# Enclosure_85x58_WS.net
KiCad netlist of a schematic drawn in EAGLE
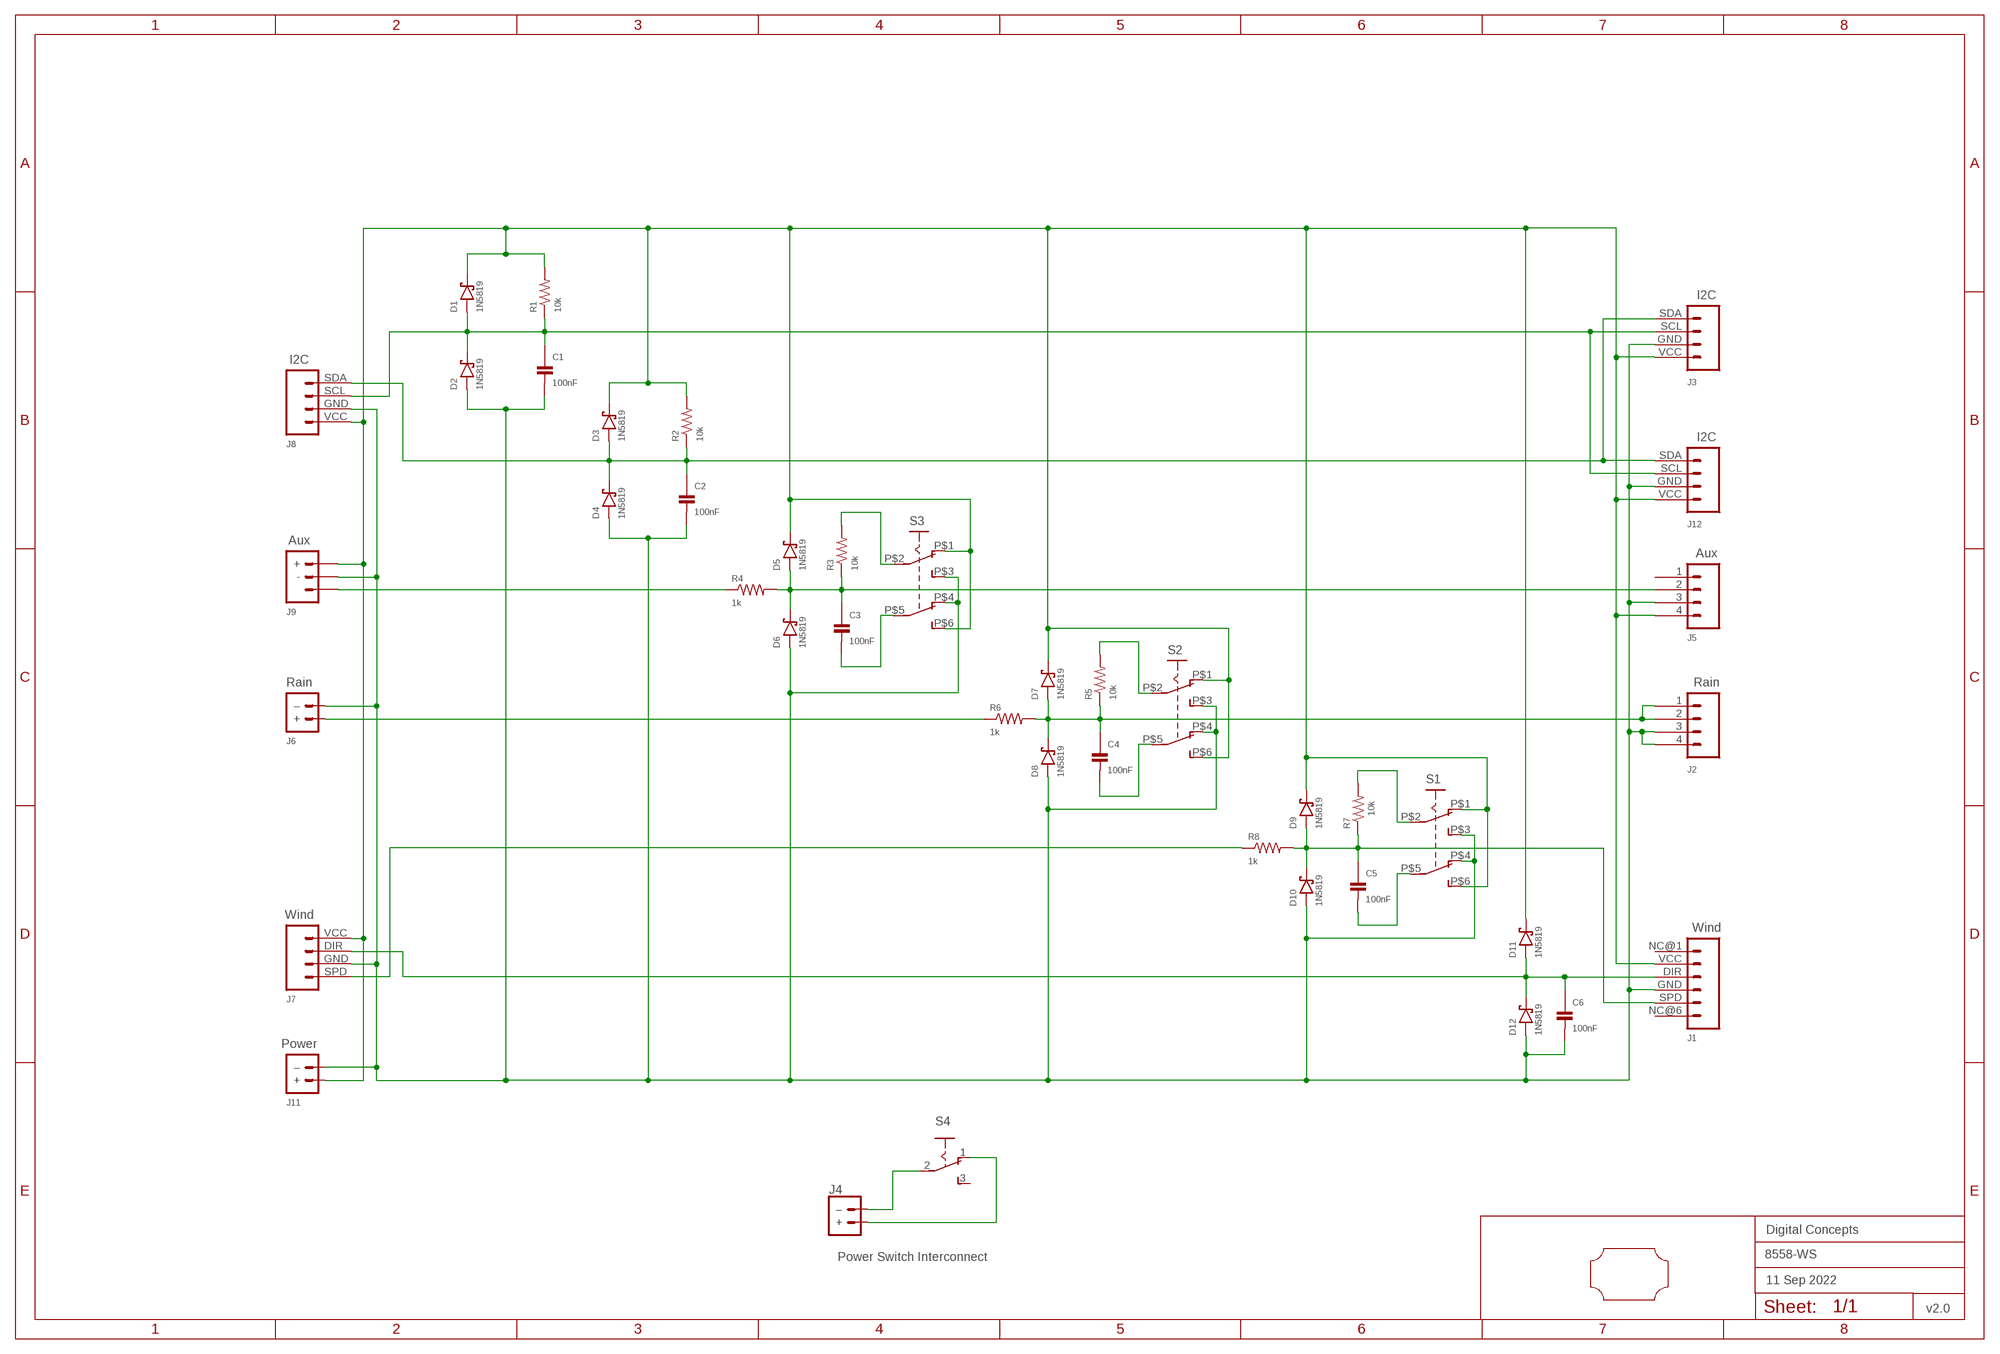
[diagram p0: schematic, sheet 1]

(export (version "E")
  (design (tool "Eeschema 10.0.6"))
  (components
    (comp (ref "C1")
      (value "100nF")
      (footprint "eagle-import:C0805-VIA-2")
      (libsource (lib "eagle-import") (part "CAPACITOR-0805-VIA-2"))
    )
    (comp (ref "C2")
      (value "100nF")
      (footprint "eagle-import:C0805-VIA-2")
      (libsource (lib "eagle-import") (part "CAPACITOR-0805-VIA-2"))
    )
    (comp (ref "C3")
      (value "100nF")
      (footprint "eagle-import:C0805")
      (libsource (lib "eagle-import") (part "CAPACITOR-0805"))
    )
    (comp (ref "C4")
      (value "100nF")
      (footprint "eagle-import:C0805")
      (libsource (lib "eagle-import") (part "CAPACITOR-0805"))
    )
    (comp (ref "C5")
      (value "100nF")
      (footprint "eagle-import:C0805")
      (libsource (lib "eagle-import") (part "CAPACITOR-0805"))
    )
    (comp (ref "C6")
      (value "100nF")
      (footprint "eagle-import:C0805-VIA-2")
      (libsource (lib "eagle-import") (part "CAPACITOR-0805-VIA-2"))
    )
    (comp (ref "D1")
      (value "1N5819")
      (footprint "eagle-import:SOD-123")
      (libsource (lib "eagle-import") (part "DIODE-SCHOTTKY-1N5819"))
    )
    (comp (ref "D2")
      (value "1N5819")
      (footprint "eagle-import:SOD-123-VIA-A")
      (libsource (lib "eagle-import") (part "DIODE-SCHOTTKY-1N5819-VIA-A"))
    )
    (comp (ref "D3")
      (value "1N5819")
      (footprint "eagle-import:SOD-123")
      (libsource (lib "eagle-import") (part "DIODE-SCHOTTKY-1N5819"))
    )
    (comp (ref "D4")
      (value "1N5819")
      (footprint "eagle-import:SOD-123-VIA-A")
      (libsource (lib "eagle-import") (part "DIODE-SCHOTTKY-1N5819-VIA-A"))
    )
    (comp (ref "D5")
      (value "1N5819")
      (footprint "eagle-import:SOD-123")
      (libsource (lib "eagle-import") (part "DIODE-SCHOTTKY-1N5819"))
    )
    (comp (ref "D6")
      (value "1N5819")
      (footprint "eagle-import:SOD-123-VIA-A")
      (libsource (lib "eagle-import") (part "DIODE-SCHOTTKY-1N5819-VIA-A"))
    )
    (comp (ref "D7")
      (value "1N5819")
      (footprint "eagle-import:SOD-123")
      (libsource (lib "eagle-import") (part "DIODE-SCHOTTKY-1N5819"))
    )
    (comp (ref "D8")
      (value "1N5819")
      (footprint "eagle-import:SOD-123-VIA-A")
      (libsource (lib "eagle-import") (part "DIODE-SCHOTTKY-1N5819-VIA-A"))
    )
    (comp (ref "D9")
      (value "1N5819")
      (footprint "eagle-import:SOD-123")
      (libsource (lib "eagle-import") (part "DIODE-SCHOTTKY-1N5819"))
    )
    (comp (ref "D10")
      (value "1N5819")
      (footprint "eagle-import:SOD-123-VIA-A")
      (libsource (lib "eagle-import") (part "DIODE-SCHOTTKY-1N5819-VIA-A"))
    )
    (comp (ref "D11")
      (value "1N5819")
      (footprint "eagle-import:SOD-123")
      (libsource (lib "eagle-import") (part "DIODE-SCHOTTKY-1N5819"))
    )
    (comp (ref "D12")
      (value "1N5819")
      (footprint "eagle-import:SOD-123-VIA-A")
      (libsource (lib "eagle-import") (part "DIODE-SCHOTTKY-1N5819-VIA-A"))
    )
    (comp (ref "J1")
      (value "Wind")
      (footprint "eagle-import:RJ11-6-VERTICAL-WIND")
      (libsource (lib "eagle-import") (part "RJ11-6P6C-VERTICAL-WIND"))
    )
    (comp (ref "J2")
      (value "Rain")
      (footprint "eagle-import:RJ11-4-VERTICAL")
      (libsource (lib "eagle-import") (part "RJ11-6P4C-VERTICAL"))
    )
    (comp (ref "J3")
      (value "I2C")
      (footprint "eagle-import:RJ11-4-VERTICAL-I2C")
      (libsource (lib "eagle-import") (part "RJ11-6P4C-VERTICAL-I2C"))
    )
    (comp (ref "J4")
      (value "JST-PH2.0-2-HORIZONTALJST-PTH-2")
      (footprint "eagle-import:JST-PH2.0-2-HORIZONTAL")
      (libsource (lib "eagle-import") (part "JST-PH2.0-2-HORIZONTALJST-PTH-2"))
    )
    (comp (ref "J5")
      (value "Aux")
      (footprint "eagle-import:RJ11-4-VERTICAL")
      (libsource (lib "eagle-import") (part "RJ11-6P4C-VERTICAL"))
    )
    (comp (ref "J6")
      (value "Rain")
      (footprint "eagle-import:JST-PH2.0-2-DUAL-POWER")
      (libsource (lib "eagle-import") (part "JST-PH2.0-2-DUALJST-PTH-2"))
    )
    (comp (ref "J7")
      (value "Wind")
      (footprint "eagle-import:JST-PH2.0-4-DUAL-WIND")
      (libsource (lib "eagle-import") (part "JST-PH2.0-4-DUAL-WIND"))
    )
    (comp (ref "J8")
      (value "I2C")
      (footprint "eagle-import:JST-PH2.0-4-DUAL-I2C")
      (libsource (lib "eagle-import") (part "JST-PH2.0-4-DUAL-I2C"))
    )
    (comp (ref "J9")
      (value "Aux")
      (footprint "eagle-import:JST-PH2.0-3-DUAL")
      (libsource (lib "eagle-import") (part "JST-PH2.0-3-DUAL"))
    )
    (comp (ref "J11")
      (value "Power")
      (footprint "eagle-import:JST-PH2.0-2-DUAL-POWER")
      (libsource (lib "eagle-import") (part "JST-PH2.0-2-DUALJST-PTH-2"))
    )
    (comp (ref "J12")
      (value "I2C")
      (footprint "eagle-import:CONN_04-I2C")
      (libsource (lib "eagle-import") (part "HEADER-1X4-I2C"))
    )
    (comp (ref "R1")
      (value "10k")
      (footprint "eagle-import:R0805-VIA-1")
      (libsource (lib "eagle-import") (part "RESISTOR-VIA-1"))
    )
    (comp (ref "R2")
      (value "10k")
      (footprint "eagle-import:R0805-VIA-1")
      (libsource (lib "eagle-import") (part "RESISTOR-VIA-1"))
    )
    (comp (ref "R3")
      (value "10k")
      (footprint "eagle-import:R0805")
      (libsource (lib "eagle-import") (part "RESISTORR0805"))
    )
    (comp (ref "R4")
      (value "1k")
      (footprint "eagle-import:R0805-VIA-1")
      (libsource (lib "eagle-import") (part "RESISTOR-VIA-1"))
    )
    (comp (ref "R5")
      (value "10k")
      (footprint "eagle-import:R0805")
      (libsource (lib "eagle-import") (part "RESISTORR0805"))
    )
    (comp (ref "R6")
      (value "1k")
      (footprint "eagle-import:R0805-VIA-1")
      (libsource (lib "eagle-import") (part "RESISTOR-VIA-1"))
    )
    (comp (ref "R7")
      (value "10k")
      (footprint "eagle-import:R0805")
      (libsource (lib "eagle-import") (part "RESISTORR0805"))
    )
    (comp (ref "R8")
      (value "1k")
      (footprint "eagle-import:R0805-VIA-1")
      (libsource (lib "eagle-import") (part "RESISTOR-VIA-1"))
    )
    (comp (ref "S1")
      (value "SWITCH-SLIDE-DPDT")
      (footprint "eagle-import:SWITCH-DPDT-SMD")
      (libsource (lib "eagle-import") (part "SWITCH-SLIDE-DPDT"))
    )
    (comp (ref "S2")
      (value "SWITCH-SLIDE-DPDT")
      (footprint "eagle-import:SWITCH-DPDT-SMD")
      (libsource (lib "eagle-import") (part "SWITCH-SLIDE-DPDT"))
    )
    (comp (ref "S3")
      (value "SWITCH-SLIDE-DPDT")
      (footprint "eagle-import:SWITCH-DPDT-SMD")
      (libsource (lib "eagle-import") (part "SWITCH-SLIDE-DPDT"))
    )
    (comp (ref "S4")
      (value "SWITCH-SLIDE-SPDT")
      (footprint "eagle-import:SWITCH-SPDT-PTH")
      (libsource (lib "eagle-import") (part "SWITCH-SLIDE-SPDT"))
    )
    (comp (ref "U$1")
      (value "PCB-OUTLINE-85X58")
      (footprint "eagle-import:PROTO-28X18-OUTLINE")
      (libsource (lib "eagle-import") (part "PCB-OUTLINE-85X58"))
    )
  )
  (nets
    (net (code "1") (name "Net-(J1-2)") (class "Default")
      (node (ref "D1") (pin "C") (pinfunction "C_C") (pintype "passive"))
      (node (ref "D11") (pin "C") (pinfunction "C_C") (pintype "passive"))
      (node (ref "D3") (pin "C") (pinfunction "C_C") (pintype "passive"))
      (node (ref "D5") (pin "C") (pinfunction "C_C") (pintype "passive"))
      (node (ref "D7") (pin "C") (pinfunction "C_C") (pintype "passive"))
      (node (ref "D9") (pin "C") (pinfunction "C_C") (pintype "passive"))
      (node (ref "J1") (pin "VCC") (pinfunction "2_VCC") (pintype "passive"))
      (node (ref "J11") (pin "+") (pinfunction "+_+") (pintype "power_in"))
      (node (ref "J12") (pin "VCC") (pinfunction "1_VCC") (pintype "passive"))
      (node (ref "J3") (pin "VCC") (pinfunction "1_VCC") (pintype "passive"))
      (node (ref "J5") (pin "4") (pinfunction "1_4") (pintype "passive"))
      (node (ref "J7") (pin "VCC") (pinfunction "1_VCC") (pintype "passive"))
      (node (ref "J8") (pin "VCC") (pinfunction "4_VCC") (pintype "passive"))
      (node (ref "J9") (pin "+") (pinfunction "+_+") (pintype "power_in"))
      (node (ref "R1") (pin "2") (pinfunction "2_2") (pintype "passive"))
      (node (ref "R2") (pin "2") (pinfunction "2_2") (pintype "passive"))
      (node (ref "S1") (pin "P$1") (pinfunction "O1_P$1") (pintype "passive"))
      (node (ref "S1") (pin "P$6") (pinfunction "S2_P$6") (pintype "passive"))
      (node (ref "S2") (pin "P$1") (pinfunction "O1_P$1") (pintype "passive"))
      (node (ref "S2") (pin "P$6") (pinfunction "S2_P$6") (pintype "passive"))
      (node (ref "S3") (pin "P$1") (pinfunction "O1_P$1") (pintype "passive"))
      (node (ref "S3") (pin "P$6") (pinfunction "S2_P$6") (pintype "passive"))
    )
    (net (code "2") (name "Net-(J1-3)") (class "Default")
      (node (ref "C6") (pin "1") (pinfunction "1_1") (pintype "passive"))
      (node (ref "D11") (pin "A") (pinfunction "A_A") (pintype "passive"))
      (node (ref "D12") (pin "C") (pinfunction "C_C") (pintype "passive"))
      (node (ref "J1") (pin "DIR") (pinfunction "3_DIR") (pintype "passive"))
      (node (ref "J7") (pin "DIR") (pinfunction "2_DIR") (pintype "passive"))
    )
    (net (code "3") (name "Net-(J1-4)") (class "Default")
      (node (ref "C1") (pin "2") (pinfunction "2_2") (pintype "passive"))
      (node (ref "C1") (pin "2@VIA") (pinfunction "2_2@VIA") (pintype "passive"))
      (node (ref "C2") (pin "2") (pinfunction "2_2") (pintype "passive"))
      (node (ref "C2") (pin "2@VIA") (pinfunction "2_2@VIA") (pintype "passive"))
      (node (ref "C6") (pin "2") (pinfunction "2_2") (pintype "passive"))
      (node (ref "C6") (pin "2@VIA") (pinfunction "2_2@VIA") (pintype "passive"))
      (node (ref "D10") (pin "A") (pinfunction "A_A") (pintype "passive"))
      (node (ref "D10") (pin "P$A") (pinfunction "A_P$A") (pintype "passive"))
      (node (ref "D12") (pin "A") (pinfunction "A_A") (pintype "passive"))
      (node (ref "D12") (pin "P$A") (pinfunction "A_P$A") (pintype "passive"))
      (node (ref "D2") (pin "A") (pinfunction "A_A") (pintype "passive"))
      (node (ref "D2") (pin "P$A") (pinfunction "A_P$A") (pintype "passive"))
      (node (ref "D4") (pin "A") (pinfunction "A_A") (pintype "passive"))
      (node (ref "D4") (pin "P$A") (pinfunction "A_P$A") (pintype "passive"))
      (node (ref "D6") (pin "A") (pinfunction "A_A") (pintype "passive"))
      (node (ref "D6") (pin "P$A") (pinfunction "A_P$A") (pintype "passive"))
      (node (ref "D8") (pin "A") (pinfunction "A_A") (pintype "passive"))
      (node (ref "D8") (pin "P$A") (pinfunction "A_P$A") (pintype "passive"))
      (node (ref "J1") (pin "GND") (pinfunction "4_GND") (pintype "passive"))
      (node (ref "J11") (pin "-") (pinfunction "–_-") (pintype "power_in"))
      (node (ref "J12") (pin "GND") (pinfunction "2_GND") (pintype "passive"))
      (node (ref "J2") (pin "3") (pinfunction "2_3") (pintype "passive"))
      (node (ref "J2") (pin "4") (pinfunction "1_4") (pintype "passive"))
      (node (ref "J3") (pin "GND") (pinfunction "2_GND") (pintype "passive"))
      (node (ref "J5") (pin "3") (pinfunction "2_3") (pintype "passive"))
      (node (ref "J6") (pin "-") (pinfunction "–_-") (pintype "power_in"))
      (node (ref "J7") (pin "GND") (pinfunction "3_GND") (pintype "passive"))
      (node (ref "J8") (pin "GND") (pinfunction "3_GND") (pintype "passive"))
      (node (ref "J9") (pin "-") (pinfunction "-_-") (pintype "power_in"))
      (node (ref "S1") (pin "P$3") (pinfunction "S1_P$3") (pintype "passive"))
      (node (ref "S1") (pin "P$4") (pinfunction "O2_P$4") (pintype "passive"))
      (node (ref "S2") (pin "P$3") (pinfunction "S1_P$3") (pintype "passive"))
      (node (ref "S2") (pin "P$4") (pinfunction "O2_P$4") (pintype "passive"))
      (node (ref "S3") (pin "P$3") (pinfunction "S1_P$3") (pintype "passive"))
      (node (ref "S3") (pin "P$4") (pinfunction "O2_P$4") (pintype "passive"))
    )
    (net (code "4") (name "Net-(J1-5)") (class "Default")
      (node (ref "C5") (pin "1") (pinfunction "1_1") (pintype "passive"))
      (node (ref "D10") (pin "C") (pinfunction "C_C") (pintype "passive"))
      (node (ref "D9") (pin "A") (pinfunction "A_A") (pintype "passive"))
      (node (ref "J1") (pin "SPD") (pinfunction "5_SPD") (pintype "passive"))
      (node (ref "R7") (pin "1") (pinfunction "1_1") (pintype "passive"))
      (node (ref "R8") (pin "2") (pinfunction "2_2") (pintype "passive"))
    )
    (net (code "5") (name "Net-(J2-3)") (class "Default")
      (node (ref "C4") (pin "1") (pinfunction "1_1") (pintype "passive"))
      (node (ref "D7") (pin "A") (pinfunction "A_A") (pintype "passive"))
      (node (ref "D8") (pin "C") (pinfunction "C_C") (pintype "passive"))
      (node (ref "J2") (pin "1") (pinfunction "4_1") (pintype "passive"))
      (node (ref "J2") (pin "2") (pinfunction "3_2") (pintype "passive"))
      (node (ref "R5") (pin "1") (pinfunction "1_1") (pintype "passive"))
      (node (ref "R6") (pin "2") (pinfunction "2_2") (pintype "passive"))
    )
    (net (code "6") (name "Net-(J4-+)") (class "Default")
      (node (ref "J4") (pin "1") (pinfunction "+_1") (pintype "power_in"))
      (node (ref "S4") (pin "1") (pinfunction "O_1") (pintype "passive"))
    )
    (net (code "7") (name "Net-(J4-–)") (class "Default")
      (node (ref "J4") (pin "2") (pinfunction "–_2") (pintype "power_in"))
      (node (ref "S4") (pin "2") (pinfunction "P_2") (pintype "passive"))
    )
    (net (code "8") (name "Net-(J5-3)") (class "Default")
      (node (ref "C3") (pin "1") (pinfunction "1_1") (pintype "passive"))
      (node (ref "D5") (pin "A") (pinfunction "A_A") (pintype "passive"))
      (node (ref "D6") (pin "C") (pinfunction "C_C") (pintype "passive"))
      (node (ref "J5") (pin "2") (pinfunction "3_2") (pintype "passive"))
      (node (ref "R3") (pin "1") (pinfunction "1_1") (pintype "passive"))
      (node (ref "R4") (pin "2") (pinfunction "2_2") (pintype "passive"))
    )
    (net (code "9") (name "Net-(J6-Pad+)") (class "Default")
      (node (ref "J6") (pin "+") (pinfunction "+_+") (pintype "power_in"))
      (node (ref "R6") (pin "1") (pinfunction "1_1") (pintype "passive"))
      (node (ref "R6") (pin "1@VIA") (pinfunction "1_1@VIA") (pintype "passive"))
    )
    (net (code "10") (name "Net-(J7-4)") (class "Default")
      (node (ref "J7") (pin "SPD") (pinfunction "4_SPD") (pintype "passive"))
      (node (ref "R8") (pin "1") (pinfunction "1_1") (pintype "passive"))
      (node (ref "R8") (pin "1@VIA") (pinfunction "1_1@VIA") (pintype "passive"))
    )
    (net (code "11") (name "Net-(J9-PadSIG)") (class "Default")
      (node (ref "J9") (pin "SIG") (pinfunction "SIG_SIG") (pintype "bidirectional"))
      (node (ref "R4") (pin "1") (pinfunction "1_1") (pintype "passive"))
      (node (ref "R4") (pin "1@VIA") (pinfunction "1_1@VIA") (pintype "passive"))
    )
    (net (code "12") (name "Net-(J12-3)") (class "Default")
      (node (ref "C1") (pin "1") (pinfunction "1_1") (pintype "passive"))
      (node (ref "D1") (pin "A") (pinfunction "A_A") (pintype "passive"))
      (node (ref "D2") (pin "C") (pinfunction "C_C") (pintype "passive"))
      (node (ref "J12") (pin "SCL") (pinfunction "3_SCL") (pintype "passive"))
      (node (ref "J3") (pin "SCL") (pinfunction "3_SCL") (pintype "passive"))
      (node (ref "J8") (pin "SCL") (pinfunction "2_SCL") (pintype "passive"))
      (node (ref "R1") (pin "1") (pinfunction "1_1") (pintype "passive"))
      (node (ref "R1") (pin "1@VIA") (pinfunction "1_1@VIA") (pintype "passive"))
    )
    (net (code "13") (name "Net-(J12-4)") (class "Default")
      (node (ref "C2") (pin "1") (pinfunction "1_1") (pintype "passive"))
      (node (ref "D3") (pin "A") (pinfunction "A_A") (pintype "passive"))
      (node (ref "D4") (pin "C") (pinfunction "C_C") (pintype "passive"))
      (node (ref "J12") (pin "SDA") (pinfunction "4_SDA") (pintype "passive"))
      (node (ref "J3") (pin "SDA") (pinfunction "4_SDA") (pintype "passive"))
      (node (ref "J8") (pin "SDA") (pinfunction "1_SDA") (pintype "passive"))
      (node (ref "R2") (pin "1") (pinfunction "1_1") (pintype "passive"))
      (node (ref "R2") (pin "1@VIA") (pinfunction "1_1@VIA") (pintype "passive"))
    )
    (net (code "14") (name "Net-(S1-P1)") (class "Default")
      (node (ref "R7") (pin "2") (pinfunction "2_2") (pintype "passive"))
      (node (ref "S1") (pin "P$2") (pinfunction "P1_P$2") (pintype "passive"))
    )
    (net (code "15") (name "Net-(S1-P2)") (class "Default")
      (node (ref "C5") (pin "2") (pinfunction "2_2") (pintype "passive"))
      (node (ref "S1") (pin "P$5") (pinfunction "P2_P$5") (pintype "passive"))
    )
    (net (code "16") (name "Net-(S2-P1)") (class "Default")
      (node (ref "R5") (pin "2") (pinfunction "2_2") (pintype "passive"))
      (node (ref "S2") (pin "P$2") (pinfunction "P1_P$2") (pintype "passive"))
    )
    (net (code "17") (name "Net-(S2-P2)") (class "Default")
      (node (ref "C4") (pin "2") (pinfunction "2_2") (pintype "passive"))
      (node (ref "S2") (pin "P$5") (pinfunction "P2_P$5") (pintype "passive"))
    )
    (net (code "18") (name "Net-(S3-P1)") (class "Default")
      (node (ref "R3") (pin "2") (pinfunction "2_2") (pintype "passive"))
      (node (ref "S3") (pin "P$2") (pinfunction "P1_P$2") (pintype "passive"))
    )
    (net (code "19") (name "Net-(S3-P2)") (class "Default")
      (node (ref "C3") (pin "2") (pinfunction "2_2") (pintype "passive"))
      (node (ref "S3") (pin "P$5") (pinfunction "P2_P$5") (pintype "passive"))
    )
    (net (code "20") (name "unconnected-(J1-1-PadNC@1)") (class "Default")
      (node (ref "J1") (pin "NC@1") (pinfunction "1_NC@1") (pintype "passive"))
    )
    (net (code "21") (name "unconnected-(J1-6-PadNC@6)") (class "Default")
      (node (ref "J1") (pin "NC@6") (pinfunction "6_NC@6") (pintype "passive"))
    )
    (net (code "22") (name "unconnected-(J5-4-Pad1)") (class "Default")
      (node (ref "J5") (pin "1") (pinfunction "4_1") (pintype "passive"))
    )
    (net (code "23") (name "unconnected-(S4-S-Pad3)") (class "Default")
      (node (ref "S4") (pin "3") (pinfunction "S_3") (pintype "passive"))
    )
  )
)
